# MCUs.net
KiCad netlist of a schematic drawn in Altium Designer
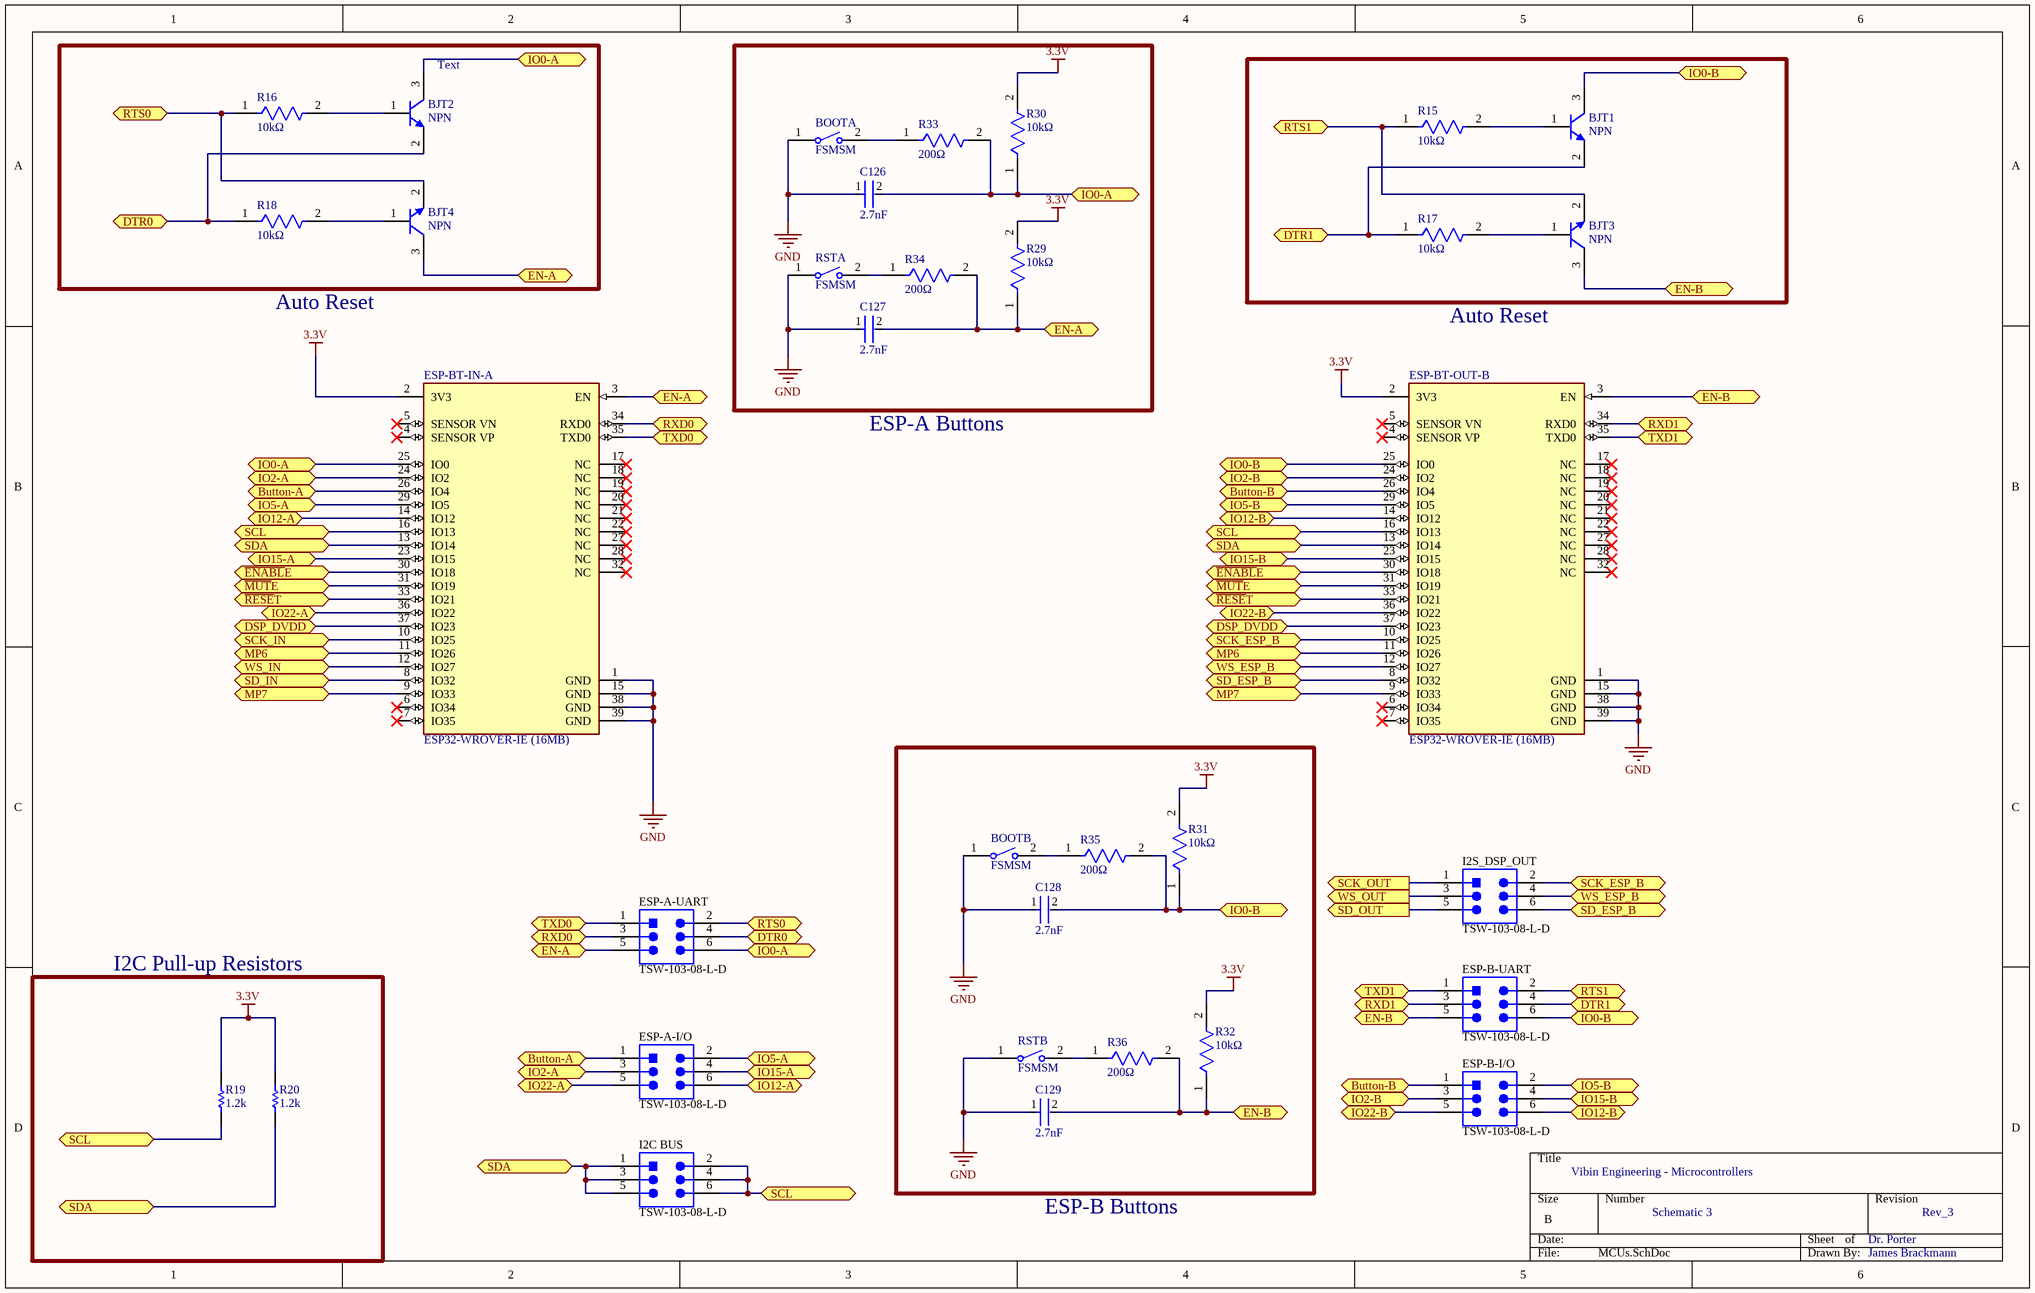
[diagram p0: MCUs.SchDoc]

(export (version "E")
  (design (tool "Eeschema 10.0.6"))
  (components
    (comp (ref "BJT1")
      (value "NPN")
      (footprint "ONSC-SOT-23-3-318-08_V")
      (description "Amplifier Transistor, NPN Silicon, 3-Pin SOT-23, Pb-Free, Tape and Reel       NSVMMBT6429LT1G")
      (fields (field (name "MANUFACTURER") "On Semiconductor") (field (name "PARTNUMBER") "NSVMMBT6429LT1G"))
      (libsource (lib "Altium Content Vault") (part "ONSC-NPN-B1E2C3-3"))
    )
    (comp (ref "BJT2")
      (value "NPN")
      (footprint "ONSC-SOT-23-3-318-08_V")
      (description "Amplifier Transistor, NPN Silicon, 3-Pin SOT-23, Pb-Free, Tape and Reel       NSVMMBT6429LT1G")
      (fields (field (name "MANUFACTURER") "On Semiconductor") (field (name "PARTNUMBER") "NSVMMBT6429LT1G"))
      (libsource (lib "Altium Content Vault") (part "ONSC-NPN-B1E2C3-3"))
    )
    (comp (ref "BJT3")
      (value "NPN")
      (footprint "ONSC-SOT-23-3-318-08_V")
      (description "Amplifier Transistor, NPN Silicon, 3-Pin SOT-23, Pb-Free, Tape and Reel       NSVMMBT6429LT1G")
      (fields (field (name "MANUFACTURER") "On Semiconductor") (field (name "PARTNUMBER") "NSVMMBT6429LT1G"))
      (libsource (lib "Altium Content Vault") (part "ONSC-NPN-B1E2C3-3"))
    )
    (comp (ref "BJT4")
      (value "NPN")
      (footprint "ONSC-SOT-23-3-318-08_V")
      (description "Amplifier Transistor, NPN Silicon, 3-Pin SOT-23, Pb-Free, Tape and Reel       NSVMMBT6429LT1G")
      (fields (field (name "MANUFACTURER") "On Semiconductor") (field (name "PARTNUMBER") "NSVMMBT6429LT1G"))
      (libsource (lib "Altium Content Vault") (part "ONSC-NPN-B1E2C3-3"))
    )
    (comp (ref "BOOTA")
      (value "FSMSM")
      (footprint "TECO-FSMSM-2_V")
      (description "FSMSM Push Button Switch, 50 mA, -35 to 85 degC, 2-Pin SMD, RoHS, Bulk        506-FSMSM")
      (fields (field (name "MANUFACTURER") "TE Connectivity"))
      (libsource (lib "Altium Content Vault") (part "SW-SPST-2_C"))
    )
    (comp (ref "BOOTB")
      (value "FSMSM")
      (footprint "TECO-FSMSM-2_V")
      (description "FSMSM Push Button Switch, 50 mA, -35 to 85 degC, 2-Pin SMD, RoHS, Bulk        506-FSMSM")
      (fields (field (name "MANUFACTURER") "TE Connectivity"))
      (libsource (lib "Altium Content Vault") (part "SW-SPST-2_C"))
    )
    (comp (ref "C126")
      (value "2.7nF")
      (footprint "FP-C0402-BB-MFG")
      (description "C0402 2,700 pF X7R 5.00% 10 V        C0402C272J8RACAUTO")
      (fields
        (field (name "OCTOPART") "https://octopart.com/c0402c272j8racauto-kemet-16435644")
        (field (name "MANUFACTURER PART NUMBER") "C0402C272J8RACAUTO")
      )
      (libsource (lib "Altium Content Vault") (part "b4654b650e69147ec39a6b967a45e02"))
    )
    (comp (ref "C127")
      (value "2.7nF")
      (footprint "FP-C0402-BB-MFG")
      (description "C0402 2,700 pF X7R 5.00% 10 V        C0402C272J8RACAUTO")
      (fields
        (field (name "OCTOPART") "https://octopart.com/c0402c272j8racauto-kemet-16435644")
        (field (name "MANUFACTURER PART NUMBER") "C0402C272J8RACAUTO")
      )
      (libsource (lib "Altium Content Vault") (part "b4654b650e69147ec39a6b967a45e02"))
    )
    (comp (ref "C128")
      (value "2.7nF")
      (footprint "FP-C0402-BB-MFG")
      (description "C0402 2,700 pF X7R 5.00% 10 V        C0402C272J8RACAUTO")
      (fields
        (field (name "OCTOPART") "https://octopart.com/c0402c272j8racauto-kemet-16435644")
        (field (name "MANUFACTURER PART NUMBER") "C0402C272J8RACAUTO")
      )
      (libsource (lib "Altium Content Vault") (part "b4654b650e69147ec39a6b967a45e02"))
    )
    (comp (ref "C129")
      (value "2.7nF")
      (footprint "FP-C0402-BB-MFG")
      (description "C0402 2,700 pF X7R 5.00% 10 V        C0402C272J8RACAUTO")
      (fields
        (field (name "OCTOPART") "https://octopart.com/c0402c272j8racauto-kemet-16435644")
        (field (name "MANUFACTURER PART NUMBER") "C0402C272J8RACAUTO")
      )
      (libsource (lib "Altium Content Vault") (part "b4654b650e69147ec39a6b967a45e02"))
    )
    (comp (ref "ESP-A-I/O")
      (value "TSW-103-08-L-D")
      (footprint "SMTC-TSW-103-08-L-D_V")
      (fields (field (name "MANUFACTURER") "Samtec"))
      (libsource (lib "Altium Content Vault") (part "CN-2P-M-R6"))
    )
    (comp (ref "ESP-A-UART")
      (value "TSW-103-08-L-D")
      (footprint "SMTC-TSW-103-08-L-D_V")
      (fields (field (name "MANUFACTURER") "Samtec"))
      (libsource (lib "Altium Content Vault") (part "CN-2P-M-R6"))
    )
    (comp (ref "ESP-B-I/O")
      (value "TSW-103-08-L-D")
      (footprint "SMTC-TSW-103-08-L-D_V")
      (fields (field (name "MANUFACTURER") "Samtec"))
      (libsource (lib "Altium Content Vault") (part "CN-2P-M-R6"))
    )
    (comp (ref "ESP-B-UART")
      (value "TSW-103-08-L-D")
      (footprint "SMTC-TSW-103-08-L-D_V")
      (fields (field (name "MANUFACTURER") "Samtec"))
      (libsource (lib "Altium Content Vault") (part "CN-2P-M-R6"))
    )
    (comp (ref "ESP-BT-IN-A")
      (value "ESP32-WROVER-IE (16MB)")
      (footprint "FP-ESP32-WROVER-IE_16MB-MFG")
      (description "RX TXRX MOD WIFI EXT IPEX SMD")
      (libsource (lib "Altium Content Vault") (part "d97c4a7c93c4f400093e1d3ec2d6536"))
    )
    (comp (ref "ESP-BT-OUT-B")
      (value "ESP32-WROVER-IE (16MB)")
      (footprint "FP-ESP32-WROVER-IE_16MB-MFG")
      (description "RX TXRX MOD WIFI EXT IPEX SMD")
      (libsource (lib "Altium Content Vault") (part "d97c4a7c93c4f400093e1d3ec2d6536"))
    )
    (comp (ref "I2C BUS")
      (value "TSW-103-08-L-D")
      (footprint "SMTC-TSW-103-08-L-D_V")
      (fields (field (name "MANUFACTURER") "Samtec"))
      (libsource (lib "Altium Content Vault") (part "CN-2P-M-R6"))
    )
    (comp (ref "I2S_DSP_OUT")
      (value "TSW-103-08-L-D")
      (footprint "SMTC-TSW-103-08-L-D_V")
      (fields (field (name "MANUFACTURER") "Samtec"))
      (libsource (lib "Altium Content Vault") (part "CN-2P-M-R6"))
    )
    (comp (ref "R15")
      (value "10kΩ")
      (footprint "FP-RC0603-0_55-IPC_C")
      (description "RES 10K OHM 1% 1/10W 0603        RC0603FR-0710KL")
      (fields (field (name "TOLERANCE") "1%"))
      (libsource (lib "Altium Content Vault") (part "1029c3af85768c4190bb7ad29bc67b5"))
    )
    (comp (ref "R16")
      (value "10kΩ")
      (footprint "FP-RC0603-0_55-IPC_C")
      (description "RES 10K OHM 1% 1/10W 0603        RC0603FR-0710KL")
      (fields (field (name "TOLERANCE") "1%"))
      (libsource (lib "Altium Content Vault") (part "1029c3af85768c4190bb7ad29bc67b5"))
    )
    (comp (ref "R17")
      (value "10kΩ")
      (footprint "FP-RC0603-0_55-IPC_C")
      (description "RES 10K OHM 1% 1/10W 0603      RC0603FR-0710KL")
      (fields (field (name "TOLERANCE") "1%"))
      (libsource (lib "Altium Content Vault") (part "1029c3af85768c4190bb7ad29bc67b5"))
    )
    (comp (ref "R18")
      (value "10kΩ")
      (footprint "FP-RC0603-0_55-IPC_C")
      (description "RES 10K OHM 1% 1/10W 0603      RC0603FR-0710KL")
      (fields (field (name "TOLERANCE") "1%"))
      (libsource (lib "Altium Content Vault") (part "1029c3af85768c4190bb7ad29bc67b5"))
    )
    (comp (ref "R19")
      (value "1.2k")
      (footprint "RESC1608X55X25LL10T15")
      (fields (field (name "TOLERANCE") "1%"))
      (libsource (lib "Altium Content Vault") (part "RES-2"))
    )
    (comp (ref "R20")
      (value "1.2k")
      (footprint "RESC1608X55X25LL10T15")
      (fields (field (name "TOLERANCE") "1%"))
      (libsource (lib "Altium Content Vault") (part "RES-2"))
    )
    (comp (ref "R29")
      (value "10kΩ")
      (footprint "FP-RC0603-0_55-IPC_C")
      (description "RES 10K OHM 1% 1/10W 0603      RC0603FR-0710KL")
      (fields (field (name "TOLERANCE") "1%"))
      (libsource (lib "Altium Content Vault") (part "1029c3af85768c4190bb7ad29bc67b5"))
    )
    (comp (ref "R30")
      (value "10kΩ")
      (footprint "FP-RC0603-0_55-IPC_C")
      (description "RES 10K OHM 1% 1/10W 0603      RC0603FR-0710KL")
      (fields (field (name "TOLERANCE") "1%"))
      (libsource (lib "Altium Content Vault") (part "1029c3af85768c4190bb7ad29bc67b5"))
    )
    (comp (ref "R31")
      (value "10kΩ")
      (footprint "FP-RC0603-0_55-IPC_C")
      (description "RES 10K OHM 1% 1/10W 0603      RC0603FR-0710KL")
      (fields (field (name "TOLERANCE") "1%"))
      (libsource (lib "Altium Content Vault") (part "1029c3af85768c4190bb7ad29bc67b5"))
    )
    (comp (ref "R32")
      (value "10kΩ")
      (footprint "FP-RC0603-0_55-IPC_C")
      (description "RES 10K OHM 1% 1/10W 0603      RC0603FR-0710KL")
      (fields (field (name "TOLERANCE") "1%"))
      (libsource (lib "Altium Content Vault") (part "1029c3af85768c4190bb7ad29bc67b5"))
    )
    (comp (ref "R33")
      (value "200Ω")
      (footprint "FP-ERJ2RK-IPC_A")
      (description "RES SMD 200 OHM 1% 1/10W 0402    ERJ-2RKF2000X")
      (fields (field (name "TOLERANCE") "1%"))
      (libsource (lib "Altium Content Vault") (part "1029c3af85768c4190bb7ad29bc67b5"))
    )
    (comp (ref "R34")
      (value "200Ω")
      (footprint "FP-ERJ2RK-IPC_A")
      (description "RES SMD 200 OHM 1% 1/10W 0402    ERJ-2RKF2000X")
      (fields (field (name "TOLERANCE") "1%"))
      (libsource (lib "Altium Content Vault") (part "1029c3af85768c4190bb7ad29bc67b5"))
    )
    (comp (ref "R35")
      (value "200Ω")
      (footprint "FP-ERJ2RK-IPC_A")
      (description "RES SMD 200 OHM 1% 1/10W 0402    ERJ-2RKF2000X")
      (fields (field (name "TOLERANCE") "1%"))
      (libsource (lib "Altium Content Vault") (part "1029c3af85768c4190bb7ad29bc67b5"))
    )
    (comp (ref "R36")
      (value "200Ω")
      (footprint "FP-ERJ2RK-IPC_A")
      (description "RES SMD 200 OHM 1% 1/10W 0402    ERJ-2RKF2000X")
      (fields (field (name "TOLERANCE") "1%"))
      (libsource (lib "Altium Content Vault") (part "1029c3af85768c4190bb7ad29bc67b5"))
    )
    (comp (ref "RSTA")
      (value "FSMSM")
      (footprint "TECO-FSMSM-2_V")
      (description "FSMSM Push Button Switch, 50 mA, -35 to 85 degC, 2-Pin SMD, RoHS, Bulk        506-FSMSM")
      (fields (field (name "MANUFACTURER") "TE Connectivity"))
      (libsource (lib "Altium Content Vault") (part "SW-SPST-2_C"))
    )
    (comp (ref "RSTB")
      (value "FSMSM")
      (footprint "TECO-FSMSM-2_V")
      (description "FSMSM Push Button Switch, 50 mA, -35 to 85 degC, 2-Pin SMD, RoHS, Bulk        506-FSMSM")
      (fields (field (name "MANUFACTURER") "TE Connectivity"))
      (libsource (lib "Altium Content Vault") (part "SW-SPST-2_C"))
    )
  )
  (nets
    (net (code "1") (name "/Button-A") (class "Default")
      (node (ref "ESP-A-I/O") (pin "1") (pinfunction "1_1") (pintype "passive"))
      (node (ref "ESP-BT-IN-A") (pin "26") (pinfunction "IO4_26") (pintype "bidirectional"))
    )
    (net (code "2") (name "/Button-B") (class "Default")
      (node (ref "ESP-B-I/O") (pin "1") (pinfunction "1_1") (pintype "passive"))
      (node (ref "ESP-BT-OUT-B") (pin "26") (pinfunction "IO4_26") (pintype "bidirectional"))
    )
    (net (code "3") (name "/DSP_DVDD") (class "Default")
      (node (ref "ESP-BT-IN-A") (pin "37") (pinfunction "IO23_37") (pintype "bidirectional"))
      (node (ref "ESP-BT-OUT-B") (pin "37") (pinfunction "IO23_37") (pintype "bidirectional"))
    )
    (net (code "4") (name "/DTR0") (class "Default")
      (node (ref "BJT2") (pin "2") (pinfunction "E_2") (pintype "passive"))
      (node (ref "ESP-A-UART") (pin "4") (pinfunction "4_4") (pintype "passive"))
      (node (ref "R18") (pin "1") (pinfunction "1_1") (pintype "passive"))
    )
    (net (code "5") (name "/DTR1") (class "Default")
      (node (ref "BJT1") (pin "2") (pinfunction "E_2") (pintype "passive"))
      (node (ref "ESP-B-UART") (pin "4") (pinfunction "4_4") (pintype "passive"))
      (node (ref "R17") (pin "1") (pinfunction "1_1") (pintype "passive"))
    )
    (net (code "6") (name "/EN-A") (class "Default")
      (node (ref "BJT4") (pin "3") (pinfunction "C_3") (pintype "passive"))
      (node (ref "C127") (pin "2") (pinfunction "2_2") (pintype "passive"))
      (node (ref "ESP-A-UART") (pin "5") (pinfunction "5_5") (pintype "passive"))
      (node (ref "ESP-BT-IN-A") (pin "3") (pinfunction "EN_3") (pintype "input"))
      (node (ref "R29") (pin "1") (pinfunction "1_1") (pintype "passive"))
      (node (ref "R34") (pin "2") (pinfunction "2_2") (pintype "passive"))
    )
    (net (code "7") (name "/EN-B") (class "Default")
      (node (ref "BJT3") (pin "3") (pinfunction "C_3") (pintype "passive"))
      (node (ref "C129") (pin "2") (pinfunction "2_2") (pintype "passive"))
      (node (ref "ESP-B-UART") (pin "5") (pinfunction "5_5") (pintype "passive"))
      (node (ref "ESP-BT-OUT-B") (pin "3") (pinfunction "EN_3") (pintype "input"))
      (node (ref "R32") (pin "1") (pinfunction "1_1") (pintype "passive"))
      (node (ref "R36") (pin "2") (pinfunction "2_2") (pintype "passive"))
    )
    (net (code "8") (name "/IO0-A") (class "Default")
      (node (ref "BJT2") (pin "3") (pinfunction "C_3") (pintype "passive"))
      (node (ref "C126") (pin "2") (pinfunction "2_2") (pintype "passive"))
      (node (ref "ESP-A-UART") (pin "6") (pinfunction "6_6") (pintype "passive"))
      (node (ref "ESP-BT-IN-A") (pin "25") (pinfunction "IO0_25") (pintype "bidirectional"))
      (node (ref "R30") (pin "1") (pinfunction "1_1") (pintype "passive"))
      (node (ref "R33") (pin "2") (pinfunction "2_2") (pintype "passive"))
    )
    (net (code "9") (name "/IO0-B") (class "Default")
      (node (ref "BJT1") (pin "3") (pinfunction "C_3") (pintype "passive"))
      (node (ref "C128") (pin "2") (pinfunction "2_2") (pintype "passive"))
      (node (ref "ESP-B-UART") (pin "6") (pinfunction "6_6") (pintype "passive"))
      (node (ref "ESP-BT-OUT-B") (pin "25") (pinfunction "IO0_25") (pintype "bidirectional"))
      (node (ref "R31") (pin "1") (pinfunction "1_1") (pintype "passive"))
      (node (ref "R35") (pin "2") (pinfunction "2_2") (pintype "passive"))
    )
    (net (code "10") (name "/IO2-A") (class "Default")
      (node (ref "ESP-A-I/O") (pin "3") (pinfunction "3_3") (pintype "passive"))
      (node (ref "ESP-BT-IN-A") (pin "24") (pinfunction "IO2_24") (pintype "bidirectional"))
    )
    (net (code "11") (name "/IO2-B") (class "Default")
      (node (ref "ESP-B-I/O") (pin "3") (pinfunction "3_3") (pintype "passive"))
      (node (ref "ESP-BT-OUT-B") (pin "24") (pinfunction "IO2_24") (pintype "bidirectional"))
    )
    (net (code "12") (name "/IO5-A") (class "Default")
      (node (ref "ESP-A-I/O") (pin "2") (pinfunction "2_2") (pintype "passive"))
      (node (ref "ESP-BT-IN-A") (pin "29") (pinfunction "IO5_29") (pintype "bidirectional"))
    )
    (net (code "13") (name "/IO5-B") (class "Default")
      (node (ref "ESP-B-I/O") (pin "2") (pinfunction "2_2") (pintype "passive"))
      (node (ref "ESP-BT-OUT-B") (pin "29") (pinfunction "IO5_29") (pintype "bidirectional"))
    )
    (net (code "14") (name "/IO12-A") (class "Default")
      (node (ref "ESP-A-I/O") (pin "6") (pinfunction "6_6") (pintype "passive"))
      (node (ref "ESP-BT-IN-A") (pin "14") (pinfunction "IO12_14") (pintype "bidirectional"))
    )
    (net (code "15") (name "/IO12-B") (class "Default")
      (node (ref "ESP-B-I/O") (pin "6") (pinfunction "6_6") (pintype "passive"))
      (node (ref "ESP-BT-OUT-B") (pin "14") (pinfunction "IO12_14") (pintype "bidirectional"))
    )
    (net (code "16") (name "/IO15-A") (class "Default")
      (node (ref "ESP-A-I/O") (pin "4") (pinfunction "4_4") (pintype "passive"))
      (node (ref "ESP-BT-IN-A") (pin "23") (pinfunction "IO15_23") (pintype "bidirectional"))
    )
    (net (code "17") (name "/IO15-B") (class "Default")
      (node (ref "ESP-B-I/O") (pin "4") (pinfunction "4_4") (pintype "passive"))
      (node (ref "ESP-BT-OUT-B") (pin "23") (pinfunction "IO15_23") (pintype "bidirectional"))
    )
    (net (code "18") (name "/IO22-A") (class "Default")
      (node (ref "ESP-A-I/O") (pin "5") (pinfunction "5_5") (pintype "passive"))
      (node (ref "ESP-BT-IN-A") (pin "36") (pinfunction "IO22_36") (pintype "bidirectional"))
    )
    (net (code "19") (name "/IO22-B") (class "Default")
      (node (ref "ESP-B-I/O") (pin "5") (pinfunction "5_5") (pintype "passive"))
      (node (ref "ESP-BT-OUT-B") (pin "36") (pinfunction "IO22_36") (pintype "bidirectional"))
    )
    (net (code "20") (name "/MP6") (class "Default")
      (node (ref "ESP-BT-IN-A") (pin "11") (pinfunction "IO26_11") (pintype "bidirectional"))
      (node (ref "ESP-BT-OUT-B") (pin "11") (pinfunction "IO26_11") (pintype "bidirectional"))
    )
    (net (code "21") (name "/MP7") (class "Default")
      (node (ref "ESP-BT-IN-A") (pin "9") (pinfunction "IO33_9") (pintype "bidirectional"))
      (node (ref "ESP-BT-OUT-B") (pin "9") (pinfunction "IO33_9") (pintype "bidirectional"))
    )
    (net (code "22") (name "/RTS0") (class "Default")
      (node (ref "BJT4") (pin "2") (pinfunction "E_2") (pintype "passive"))
      (node (ref "ESP-A-UART") (pin "2") (pinfunction "2_2") (pintype "passive"))
      (node (ref "R16") (pin "1") (pinfunction "1_1") (pintype "passive"))
    )
    (net (code "23") (name "/RTS1") (class "Default")
      (node (ref "BJT3") (pin "2") (pinfunction "E_2") (pintype "passive"))
      (node (ref "ESP-B-UART") (pin "2") (pinfunction "2_2") (pintype "passive"))
      (node (ref "R15") (pin "1") (pinfunction "1_1") (pintype "passive"))
    )
    (net (code "24") (name "/RXD0") (class "Default")
      (node (ref "ESP-A-UART") (pin "3") (pinfunction "3_3") (pintype "passive"))
      (node (ref "ESP-BT-IN-A") (pin "34") (pinfunction "RXD0_34") (pintype "bidirectional"))
    )
    (net (code "25") (name "/RXD1") (class "Default")
      (node (ref "ESP-B-UART") (pin "3") (pinfunction "3_3") (pintype "passive"))
      (node (ref "ESP-BT-OUT-B") (pin "34") (pinfunction "RXD0_34") (pintype "bidirectional"))
    )
    (net (code "26") (name "/SCK_ESP_B") (class "Default")
      (node (ref "ESP-BT-OUT-B") (pin "10") (pinfunction "IO25_10") (pintype "bidirectional"))
      (node (ref "I2S_DSP_OUT") (pin "2") (pinfunction "2_2") (pintype "passive"))
    )
    (net (code "27") (name "/SCK_IN") (class "Default")
      (node (ref "ESP-BT-IN-A") (pin "10") (pinfunction "IO25_10") (pintype "bidirectional"))
    )
    (net (code "28") (name "/SCK_OUT") (class "Default")
      (node (ref "I2S_DSP_OUT") (pin "1") (pinfunction "1_1") (pintype "passive"))
    )
    (net (code "29") (name "/SCL") (class "Default")
      (node (ref "ESP-BT-IN-A") (pin "16") (pinfunction "IO13_16") (pintype "bidirectional"))
      (node (ref "ESP-BT-OUT-B") (pin "16") (pinfunction "IO13_16") (pintype "bidirectional"))
      (node (ref "I2C BUS") (pin "2") (pinfunction "2_2") (pintype "passive"))
      (node (ref "I2C BUS") (pin "4") (pinfunction "4_4") (pintype "passive"))
      (node (ref "I2C BUS") (pin "6") (pinfunction "6_6") (pintype "passive"))
      (node (ref "R19") (pin "1") (pinfunction "1_1") (pintype "passive"))
    )
    (net (code "30") (name "/SDA") (class "Default")
      (node (ref "ESP-BT-IN-A") (pin "13") (pinfunction "IO14_13") (pintype "bidirectional"))
      (node (ref "ESP-BT-OUT-B") (pin "13") (pinfunction "IO14_13") (pintype "bidirectional"))
      (node (ref "I2C BUS") (pin "1") (pinfunction "1_1") (pintype "passive"))
      (node (ref "I2C BUS") (pin "3") (pinfunction "3_3") (pintype "passive"))
      (node (ref "I2C BUS") (pin "5") (pinfunction "5_5") (pintype "passive"))
      (node (ref "R20") (pin "1") (pinfunction "1_1") (pintype "passive"))
    )
    (net (code "31") (name "/SD_ESP_B") (class "Default")
      (node (ref "ESP-BT-OUT-B") (pin "8") (pinfunction "IO32_8") (pintype "bidirectional"))
      (node (ref "I2S_DSP_OUT") (pin "6") (pinfunction "6_6") (pintype "passive"))
    )
    (net (code "32") (name "/SD_IN") (class "Default")
      (node (ref "ESP-BT-IN-A") (pin "8") (pinfunction "IO32_8") (pintype "bidirectional"))
    )
    (net (code "33") (name "/SD_OUT") (class "Default")
      (node (ref "I2S_DSP_OUT") (pin "5") (pinfunction "5_5") (pintype "passive"))
    )
    (net (code "34") (name "/TXD0") (class "Default")
      (node (ref "ESP-A-UART") (pin "1") (pinfunction "1_1") (pintype "passive"))
      (node (ref "ESP-BT-IN-A") (pin "35") (pinfunction "TXD0_35") (pintype "bidirectional"))
    )
    (net (code "35") (name "/TXD1") (class "Default")
      (node (ref "ESP-B-UART") (pin "1") (pinfunction "1_1") (pintype "passive"))
      (node (ref "ESP-BT-OUT-B") (pin "35") (pinfunction "TXD0_35") (pintype "bidirectional"))
    )
    (net (code "36") (name "/WS_ESP_B") (class "Default")
      (node (ref "ESP-BT-OUT-B") (pin "12") (pinfunction "IO27_12") (pintype "bidirectional"))
      (node (ref "I2S_DSP_OUT") (pin "4") (pinfunction "4_4") (pintype "passive"))
    )
    (net (code "37") (name "/WS_IN") (class "Default")
      (node (ref "ESP-BT-IN-A") (pin "12") (pinfunction "IO27_12") (pintype "bidirectional"))
    )
    (net (code "38") (name "/WS_OUT") (class "Default")
      (node (ref "I2S_DSP_OUT") (pin "3") (pinfunction "3_3") (pintype "passive"))
    )
    (net (code "39") (name "/~{ENABL}E") (class "Default")
      (node (ref "ESP-BT-IN-A") (pin "30") (pinfunction "IO18_30") (pintype "bidirectional"))
      (node (ref "ESP-BT-OUT-B") (pin "30") (pinfunction "IO18_30") (pintype "bidirectional"))
    )
    (net (code "40") (name "/~{MUT}E") (class "Default")
      (node (ref "ESP-BT-IN-A") (pin "31") (pinfunction "IO19_31") (pintype "bidirectional"))
      (node (ref "ESP-BT-OUT-B") (pin "31") (pinfunction "IO19_31") (pintype "bidirectional"))
    )
    (net (code "41") (name "/~{RESE}T") (class "Default")
      (node (ref "ESP-BT-IN-A") (pin "33") (pinfunction "IO21_33") (pintype "bidirectional"))
      (node (ref "ESP-BT-OUT-B") (pin "33") (pinfunction "IO21_33") (pintype "bidirectional"))
    )
    (net (code "42") (name "3.3V") (class "Default")
      (node (ref "ESP-BT-IN-A") (pin "2") (pinfunction "3V3_2") (pintype "power_in"))
      (node (ref "ESP-BT-OUT-B") (pin "2") (pinfunction "3V3_2") (pintype "power_in"))
      (node (ref "R19") (pin "2") (pinfunction "2_2") (pintype "passive"))
      (node (ref "R20") (pin "2") (pinfunction "2_2") (pintype "passive"))
      (node (ref "R29") (pin "2") (pinfunction "2_2") (pintype "passive"))
      (node (ref "R30") (pin "2") (pinfunction "2_2") (pintype "passive"))
      (node (ref "R31") (pin "2") (pinfunction "2_2") (pintype "passive"))
      (node (ref "R32") (pin "2") (pinfunction "2_2") (pintype "passive"))
    )
    (net (code "43") (name "GND") (class "Default")
      (node (ref "BOOTA") (pin "1") (pinfunction "1_1") (pintype "passive"))
      (node (ref "BOOTB") (pin "1") (pinfunction "1_1") (pintype "passive"))
      (node (ref "C126") (pin "1") (pinfunction "1_1") (pintype "passive"))
      (node (ref "C127") (pin "1") (pinfunction "1_1") (pintype "passive"))
      (node (ref "C128") (pin "1") (pinfunction "1_1") (pintype "passive"))
      (node (ref "C129") (pin "1") (pinfunction "1_1") (pintype "passive"))
      (node (ref "ESP-BT-IN-A") (pin "1") (pinfunction "GND_1") (pintype "power_in"))
      (node (ref "ESP-BT-IN-A") (pin "15") (pinfunction "GND_15") (pintype "power_in"))
      (node (ref "ESP-BT-IN-A") (pin "38") (pinfunction "GND_38") (pintype "power_in"))
      (node (ref "ESP-BT-IN-A") (pin "39") (pinfunction "GND_39") (pintype "power_in"))
      (node (ref "ESP-BT-OUT-B") (pin "1") (pinfunction "GND_1") (pintype "power_in"))
      (node (ref "ESP-BT-OUT-B") (pin "15") (pinfunction "GND_15") (pintype "power_in"))
      (node (ref "ESP-BT-OUT-B") (pin "38") (pinfunction "GND_38") (pintype "power_in"))
      (node (ref "ESP-BT-OUT-B") (pin "39") (pinfunction "GND_39") (pintype "power_in"))
      (node (ref "RSTA") (pin "1") (pinfunction "1_1") (pintype "passive"))
      (node (ref "RSTB") (pin "1") (pinfunction "1_1") (pintype "passive"))
    )
    (net (code "44") (name "Net-(BJT1-B)") (class "Default")
      (node (ref "BJT1") (pin "1") (pinfunction "B_1") (pintype "passive"))
      (node (ref "R15") (pin "2") (pinfunction "2_2") (pintype "passive"))
    )
    (net (code "45") (name "Net-(BJT2-B)") (class "Default")
      (node (ref "BJT2") (pin "1") (pinfunction "B_1") (pintype "passive"))
      (node (ref "R16") (pin "2") (pinfunction "2_2") (pintype "passive"))
    )
    (net (code "46") (name "Net-(BJT3-B)") (class "Default")
      (node (ref "BJT3") (pin "1") (pinfunction "B_1") (pintype "passive"))
      (node (ref "R17") (pin "2") (pinfunction "2_2") (pintype "passive"))
    )
    (net (code "47") (name "Net-(BJT4-B)") (class "Default")
      (node (ref "BJT4") (pin "1") (pinfunction "B_1") (pintype "passive"))
      (node (ref "R18") (pin "2") (pinfunction "2_2") (pintype "passive"))
    )
    (net (code "48") (name "Net-(BOOTA-Pad2)") (class "Default")
      (node (ref "BOOTA") (pin "2") (pinfunction "2_2") (pintype "passive"))
      (node (ref "R33") (pin "1") (pinfunction "1_1") (pintype "passive"))
    )
    (net (code "49") (name "Net-(BOOTB-Pad2)") (class "Default")
      (node (ref "BOOTB") (pin "2") (pinfunction "2_2") (pintype "passive"))
      (node (ref "R35") (pin "1") (pinfunction "1_1") (pintype "passive"))
    )
    (net (code "50") (name "Net-(R34-Pad1)") (class "Default")
      (node (ref "R34") (pin "1") (pinfunction "1_1") (pintype "passive"))
      (node (ref "RSTA") (pin "2") (pinfunction "2_2") (pintype "passive"))
    )
    (net (code "51") (name "Net-(R36-Pad1)") (class "Default")
      (node (ref "R36") (pin "1") (pinfunction "1_1") (pintype "passive"))
      (node (ref "RSTB") (pin "2") (pinfunction "2_2") (pintype "passive"))
    )
    (net (code "52") (name "unconnected-(ESP-BT-IN-A-IO34-Pad6)") (class "Default")
      (node (ref "ESP-BT-IN-A") (pin "6") (pinfunction "IO34_6") (pintype "bidirectional+no_connect"))
    )
    (net (code "53") (name "unconnected-(ESP-BT-IN-A-IO35-Pad7)") (class "Default")
      (node (ref "ESP-BT-IN-A") (pin "7") (pinfunction "IO35_7") (pintype "bidirectional+no_connect"))
    )
    (net (code "54") (name "unconnected-(ESP-BT-IN-A-NC-Pad17)") (class "Default")
      (node (ref "ESP-BT-IN-A") (pin "17") (pinfunction "NC_17") (pintype "passive+no_connect"))
    )
    (net (code "55") (name "unconnected-(ESP-BT-IN-A-NC-Pad18)") (class "Default")
      (node (ref "ESP-BT-IN-A") (pin "18") (pinfunction "NC_18") (pintype "passive+no_connect"))
    )
    (net (code "56") (name "unconnected-(ESP-BT-IN-A-NC-Pad19)") (class "Default")
      (node (ref "ESP-BT-IN-A") (pin "19") (pinfunction "NC_19") (pintype "passive+no_connect"))
    )
    (net (code "57") (name "unconnected-(ESP-BT-IN-A-NC-Pad20)") (class "Default")
      (node (ref "ESP-BT-IN-A") (pin "20") (pinfunction "NC_20") (pintype "passive+no_connect"))
    )
    (net (code "58") (name "unconnected-(ESP-BT-IN-A-NC-Pad21)") (class "Default")
      (node (ref "ESP-BT-IN-A") (pin "21") (pinfunction "NC_21") (pintype "passive+no_connect"))
    )
    (net (code "59") (name "unconnected-(ESP-BT-IN-A-NC-Pad22)") (class "Default")
      (node (ref "ESP-BT-IN-A") (pin "22") (pinfunction "NC_22") (pintype "passive+no_connect"))
    )
    (net (code "60") (name "unconnected-(ESP-BT-IN-A-NC-Pad27)") (class "Default")
      (node (ref "ESP-BT-IN-A") (pin "27") (pinfunction "NC_27") (pintype "passive+no_connect"))
    )
    (net (code "61") (name "unconnected-(ESP-BT-IN-A-NC-Pad28)") (class "Default")
      (node (ref "ESP-BT-IN-A") (pin "28") (pinfunction "NC_28") (pintype "passive+no_connect"))
    )
    (net (code "62") (name "unconnected-(ESP-BT-IN-A-NC-Pad32)") (class "Default")
      (node (ref "ESP-BT-IN-A") (pin "32") (pinfunction "NC_32") (pintype "passive+no_connect"))
    )
    (net (code "63") (name "unconnected-(ESP-BT-IN-A-SENSOR_VN-Pad5)") (class "Default")
      (node (ref "ESP-BT-IN-A") (pin "5") (pinfunction "SENSOR_VN_5") (pintype "bidirectional+no_connect"))
    )
    (net (code "64") (name "unconnected-(ESP-BT-IN-A-SENSOR_VP-Pad4)") (class "Default")
      (node (ref "ESP-BT-IN-A") (pin "4") (pinfunction "SENSOR_VP_4") (pintype "bidirectional+no_connect"))
    )
    (net (code "65") (name "unconnected-(ESP-BT-OUT-B-IO34-Pad6)") (class "Default")
      (node (ref "ESP-BT-OUT-B") (pin "6") (pinfunction "IO34_6") (pintype "bidirectional+no_connect"))
    )
    (net (code "66") (name "unconnected-(ESP-BT-OUT-B-IO35-Pad7)") (class "Default")
      (node (ref "ESP-BT-OUT-B") (pin "7") (pinfunction "IO35_7") (pintype "bidirectional+no_connect"))
    )
    (net (code "67") (name "unconnected-(ESP-BT-OUT-B-NC-Pad17)") (class "Default")
      (node (ref "ESP-BT-OUT-B") (pin "17") (pinfunction "NC_17") (pintype "passive+no_connect"))
    )
    (net (code "68") (name "unconnected-(ESP-BT-OUT-B-NC-Pad18)") (class "Default")
      (node (ref "ESP-BT-OUT-B") (pin "18") (pinfunction "NC_18") (pintype "passive+no_connect"))
    )
    (net (code "69") (name "unconnected-(ESP-BT-OUT-B-NC-Pad19)") (class "Default")
      (node (ref "ESP-BT-OUT-B") (pin "19") (pinfunction "NC_19") (pintype "passive+no_connect"))
    )
    (net (code "70") (name "unconnected-(ESP-BT-OUT-B-NC-Pad20)") (class "Default")
      (node (ref "ESP-BT-OUT-B") (pin "20") (pinfunction "NC_20") (pintype "passive+no_connect"))
    )
    (net (code "71") (name "unconnected-(ESP-BT-OUT-B-NC-Pad21)") (class "Default")
      (node (ref "ESP-BT-OUT-B") (pin "21") (pinfunction "NC_21") (pintype "passive+no_connect"))
    )
    (net (code "72") (name "unconnected-(ESP-BT-OUT-B-NC-Pad22)") (class "Default")
      (node (ref "ESP-BT-OUT-B") (pin "22") (pinfunction "NC_22") (pintype "passive+no_connect"))
    )
    (net (code "73") (name "unconnected-(ESP-BT-OUT-B-NC-Pad27)") (class "Default")
      (node (ref "ESP-BT-OUT-B") (pin "27") (pinfunction "NC_27") (pintype "passive+no_connect"))
    )
    (net (code "74") (name "unconnected-(ESP-BT-OUT-B-NC-Pad28)") (class "Default")
      (node (ref "ESP-BT-OUT-B") (pin "28") (pinfunction "NC_28") (pintype "passive+no_connect"))
    )
    (net (code "75") (name "unconnected-(ESP-BT-OUT-B-NC-Pad32)") (class "Default")
      (node (ref "ESP-BT-OUT-B") (pin "32") (pinfunction "NC_32") (pintype "passive+no_connect"))
    )
    (net (code "76") (name "unconnected-(ESP-BT-OUT-B-SENSOR_VN-Pad5)") (class "Default")
      (node (ref "ESP-BT-OUT-B") (pin "5") (pinfunction "SENSOR_VN_5") (pintype "bidirectional+no_connect"))
    )
    (net (code "77") (name "unconnected-(ESP-BT-OUT-B-SENSOR_VP-Pad4)") (class "Default")
      (node (ref "ESP-BT-OUT-B") (pin "4") (pinfunction "SENSOR_VP_4") (pintype "bidirectional+no_connect"))
    )
  )
)
